# 07_-_QSFP28_2.net
KiCad netlist of a schematic drawn in Altium Designer
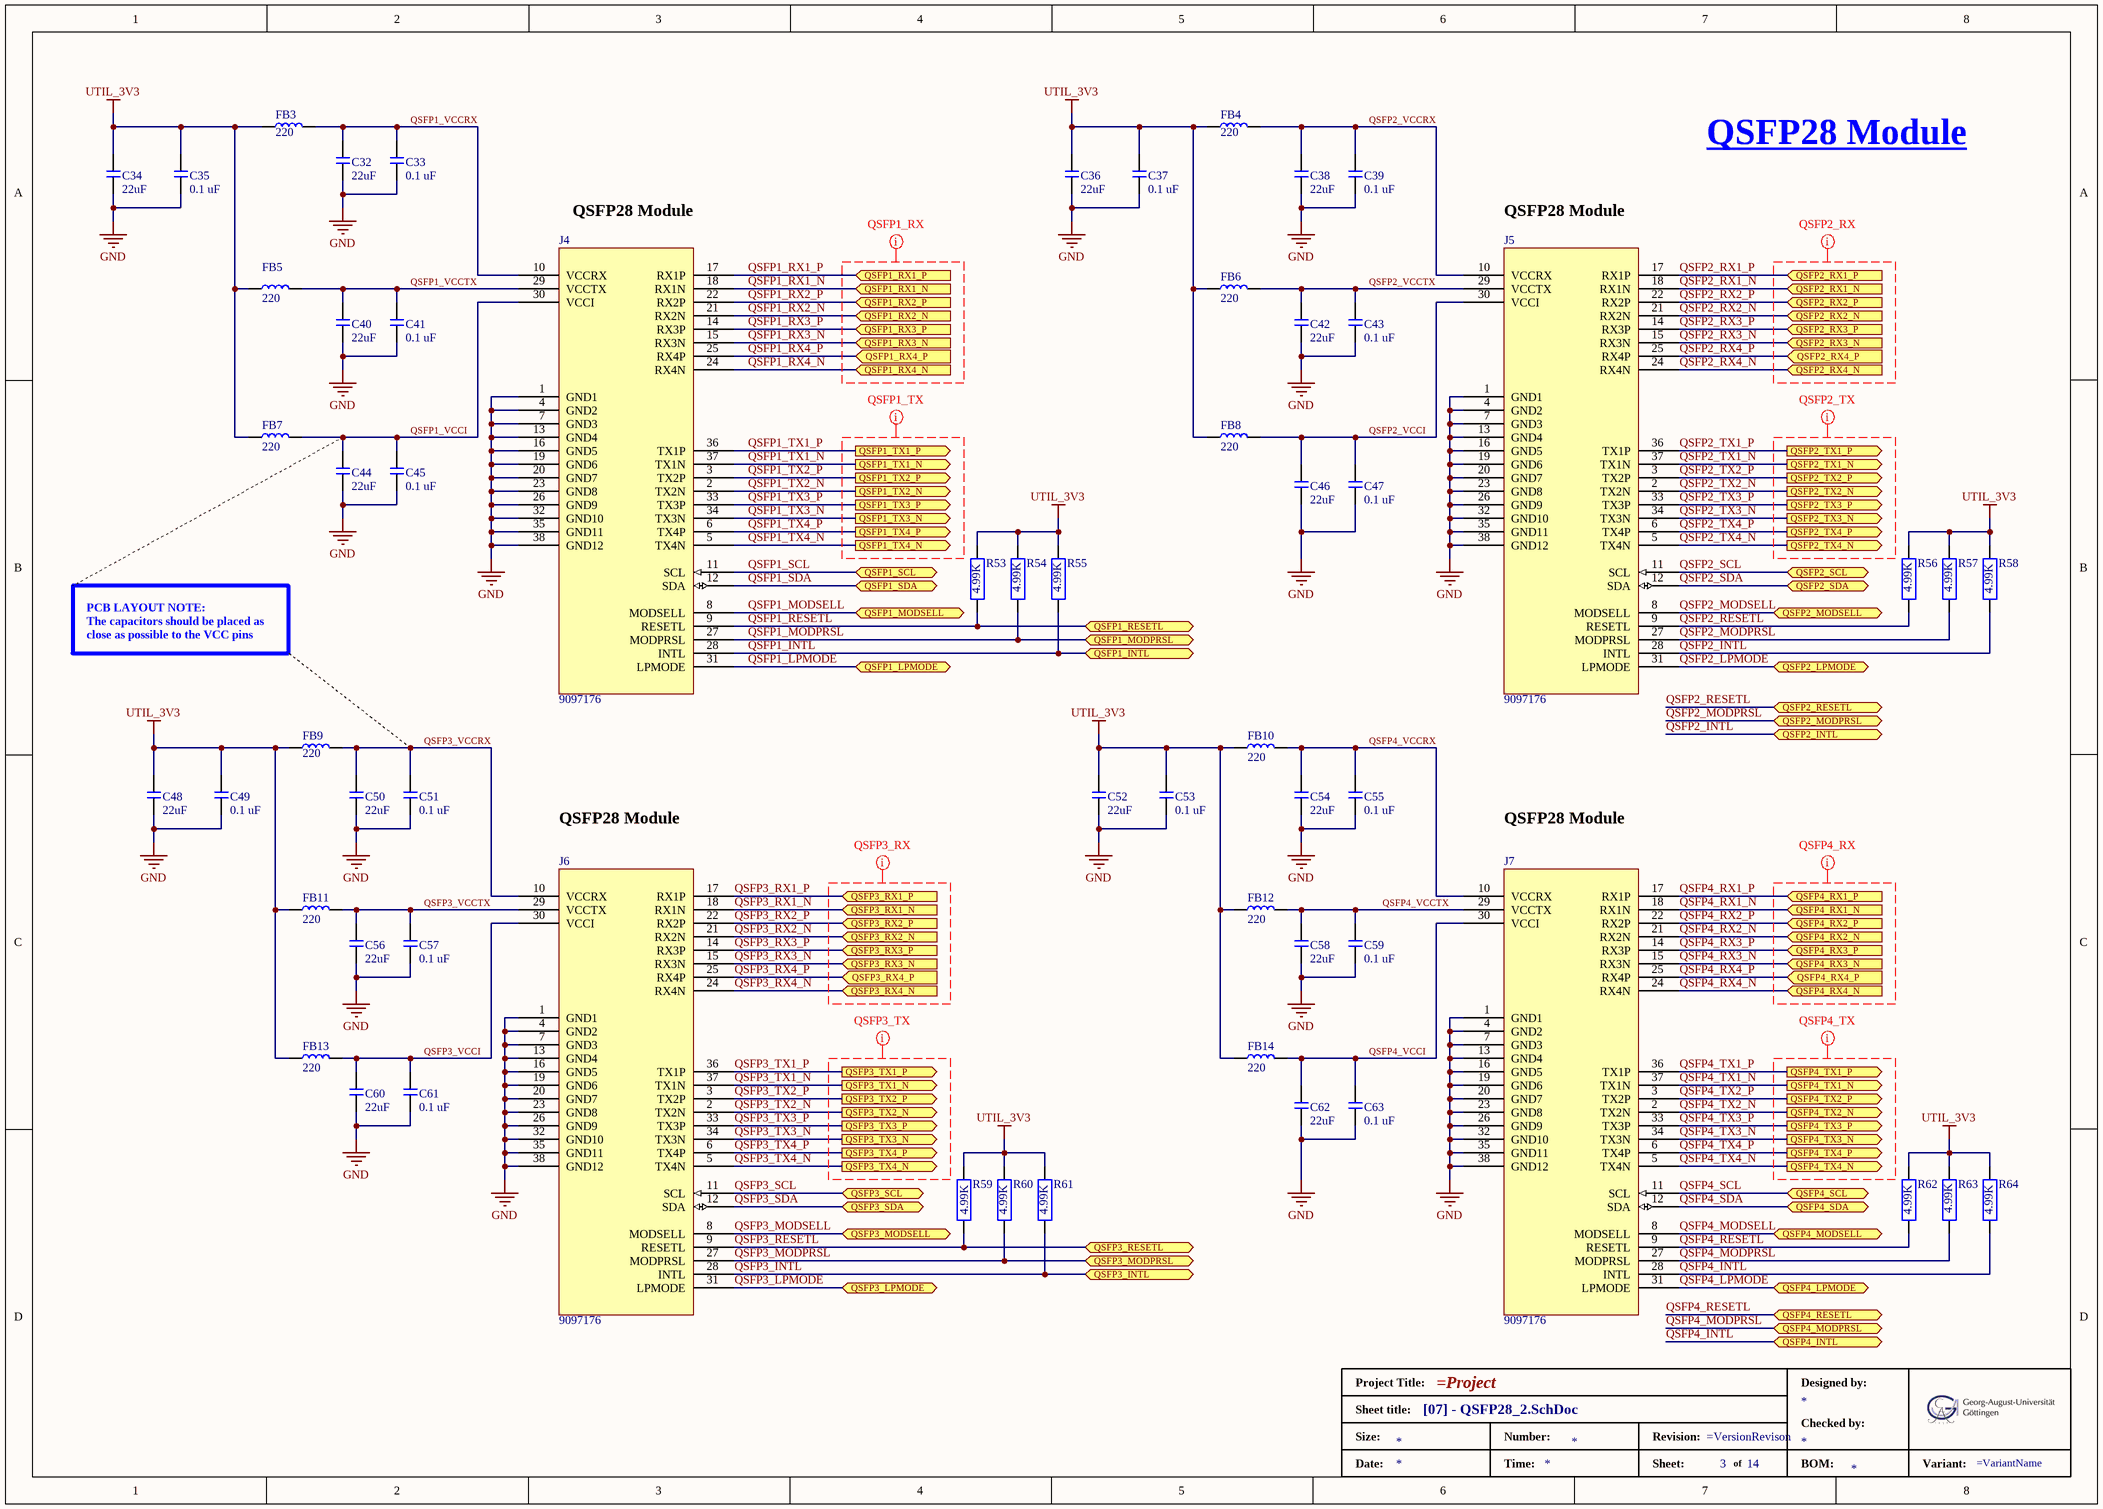
[diagram p0: [07] - QSFP28_2.SchDoc]

(export (version "E")
  (design (tool "Eeschema 10.0.6"))
  (components
    (comp (ref "*")
      (value "Standard Title Block")
      (fields
        (field (name "SIZE") "*")
        (field (name "BOM") "*")
        (field (name "DESIGNEDBY") "*")
        (field (name "DW") "*")
        (field (name "CHECKEDBY") "*")
      )
      (libsource (lib "QSFP28_FMC_lib") (part "Title_Block"))
    )
    (comp (ref "C32")
      (value "22uF")
      (footprint "C2012")
      (description "Cap Series 0805 22 uF 35 V ±20 % Tolerance X5R SMT Multilayer Ceramic Capacitor")
      (fields
        (field (name "MANUFACTURER") "TDK")
        (field (name "MANUFACTURER PART NUMBER") "C2012X5R1V226M125AC")
      )
      (libsource (lib "QSFP28_FMC_lib") (part "C2012X5R1V226M125AC"))
    )
    (comp (ref "C33")
      (value "0.1 uF")
      (footprint "C0402")
      (description "Cap 0402 0.1 uF 50 V ±10 % Tolerance X7R Surface Mount Multilayer Ceramic Capacitor")
      (fields
        (field (name "MANUFACTURER") "Taiyo Yuden")
        (field (name "MANUFACTURER PART NUMBER") "UMK105B7104KV-FR")
      )
      (libsource (lib "QSFP28_FMC_lib") (part "UMK105B7104KV-FR"))
    )
    (comp (ref "C34")
      (value "22uF")
      (footprint "C2012")
      (description "Cap Series 0805 22 uF 35 V ±20 % Tolerance X5R SMT Multilayer Ceramic Capacitor")
      (fields
        (field (name "MANUFACTURER") "TDK")
        (field (name "MANUFACTURER PART NUMBER") "C2012X5R1V226M125AC")
      )
      (libsource (lib "QSFP28_FMC_lib") (part "C2012X5R1V226M125AC"))
    )
    (comp (ref "C35")
      (value "0.1 uF")
      (footprint "C0402")
      (description "Cap 0402 0.1 uF 50 V ±10 % Tolerance X7R Surface Mount Multilayer Ceramic Capacitor")
      (fields
        (field (name "MANUFACTURER") "Taiyo Yuden")
        (field (name "MANUFACTURER PART NUMBER") "UMK105B7104KV-FR")
      )
      (libsource (lib "QSFP28_FMC_lib") (part "UMK105B7104KV-FR"))
    )
    (comp (ref "C36")
      (value "22uF")
      (footprint "C2012")
      (description "Cap Series 0805 22 uF 35 V ±20 % Tolerance X5R SMT Multilayer Ceramic Capacitor")
      (fields
        (field (name "MANUFACTURER") "TDK")
        (field (name "MANUFACTURER PART NUMBER") "C2012X5R1V226M125AC")
      )
      (libsource (lib "QSFP28_FMC_lib") (part "C2012X5R1V226M125AC"))
    )
    (comp (ref "C37")
      (value "0.1 uF")
      (footprint "C0402")
      (description "Cap 0402 0.1 uF 50 V ±10 % Tolerance X7R Surface Mount Multilayer Ceramic Capacitor")
      (fields
        (field (name "MANUFACTURER") "Taiyo Yuden")
        (field (name "MANUFACTURER PART NUMBER") "UMK105B7104KV-FR")
      )
      (libsource (lib "QSFP28_FMC_lib") (part "UMK105B7104KV-FR"))
    )
    (comp (ref "C38")
      (value "22uF")
      (footprint "C2012")
      (description "Cap Series 0805 22 uF 35 V ±20 % Tolerance X5R SMT Multilayer Ceramic Capacitor")
      (fields
        (field (name "MANUFACTURER") "TDK")
        (field (name "MANUFACTURER PART NUMBER") "C2012X5R1V226M125AC")
      )
      (libsource (lib "QSFP28_FMC_lib") (part "C2012X5R1V226M125AC"))
    )
    (comp (ref "C39")
      (value "0.1 uF")
      (footprint "C0402")
      (description "Cap 0402 0.1 uF 50 V ±10 % Tolerance X7R Surface Mount Multilayer Ceramic Capacitor")
      (fields
        (field (name "MANUFACTURER") "Taiyo Yuden")
        (field (name "MANUFACTURER PART NUMBER") "UMK105B7104KV-FR")
      )
      (libsource (lib "QSFP28_FMC_lib") (part "UMK105B7104KV-FR"))
    )
    (comp (ref "C40")
      (value "22uF")
      (footprint "C2012")
      (description "Cap Series 0805 22 uF 35 V ±20 % Tolerance X5R SMT Multilayer Ceramic Capacitor")
      (fields
        (field (name "MANUFACTURER") "TDK")
        (field (name "MANUFACTURER PART NUMBER") "C2012X5R1V226M125AC")
      )
      (libsource (lib "QSFP28_FMC_lib") (part "C2012X5R1V226M125AC"))
    )
    (comp (ref "C41")
      (value "0.1 uF")
      (footprint "C0402")
      (description "Cap 0402 0.1 uF 50 V ±10 % Tolerance X7R Surface Mount Multilayer Ceramic Capacitor")
      (fields
        (field (name "MANUFACTURER") "Taiyo Yuden")
        (field (name "MANUFACTURER PART NUMBER") "UMK105B7104KV-FR")
      )
      (libsource (lib "QSFP28_FMC_lib") (part "UMK105B7104KV-FR"))
    )
    (comp (ref "C42")
      (value "22uF")
      (footprint "C2012")
      (description "Cap Series 0805 22 uF 35 V ±20 % Tolerance X5R SMT Multilayer Ceramic Capacitor")
      (fields
        (field (name "MANUFACTURER") "TDK")
        (field (name "MANUFACTURER PART NUMBER") "C2012X5R1V226M125AC")
      )
      (libsource (lib "QSFP28_FMC_lib") (part "C2012X5R1V226M125AC"))
    )
    (comp (ref "C43")
      (value "0.1 uF")
      (footprint "C0402")
      (description "Cap 0402 0.1 uF 50 V ±10 % Tolerance X7R Surface Mount Multilayer Ceramic Capacitor")
      (fields
        (field (name "MANUFACTURER") "Taiyo Yuden")
        (field (name "MANUFACTURER PART NUMBER") "UMK105B7104KV-FR")
      )
      (libsource (lib "QSFP28_FMC_lib") (part "UMK105B7104KV-FR"))
    )
    (comp (ref "C44")
      (value "22uF")
      (footprint "C2012")
      (description "Cap Series 0805 22 uF 35 V ±20 % Tolerance X5R SMT Multilayer Ceramic Capacitor")
      (fields
        (field (name "MANUFACTURER") "TDK")
        (field (name "MANUFACTURER PART NUMBER") "C2012X5R1V226M125AC")
      )
      (libsource (lib "QSFP28_FMC_lib") (part "C2012X5R1V226M125AC"))
    )
    (comp (ref "C45")
      (value "0.1 uF")
      (footprint "C0402")
      (description "Cap 0402 0.1 uF 50 V ±10 % Tolerance X7R Surface Mount Multilayer Ceramic Capacitor")
      (fields
        (field (name "MANUFACTURER") "Taiyo Yuden")
        (field (name "MANUFACTURER PART NUMBER") "UMK105B7104KV-FR")
      )
      (libsource (lib "QSFP28_FMC_lib") (part "UMK105B7104KV-FR"))
    )
    (comp (ref "C46")
      (value "22uF")
      (footprint "C2012")
      (description "Cap Series 0805 22 uF 35 V ±20 % Tolerance X5R SMT Multilayer Ceramic Capacitor")
      (fields
        (field (name "MANUFACTURER") "TDK")
        (field (name "MANUFACTURER PART NUMBER") "C2012X5R1V226M125AC")
      )
      (libsource (lib "QSFP28_FMC_lib") (part "C2012X5R1V226M125AC"))
    )
    (comp (ref "C47")
      (value "0.1 uF")
      (footprint "C0402")
      (description "Cap 0402 0.1 uF 50 V ±10 % Tolerance X7R Surface Mount Multilayer Ceramic Capacitor")
      (fields
        (field (name "MANUFACTURER") "Taiyo Yuden")
        (field (name "MANUFACTURER PART NUMBER") "UMK105B7104KV-FR")
      )
      (libsource (lib "QSFP28_FMC_lib") (part "UMK105B7104KV-FR"))
    )
    (comp (ref "C48")
      (value "22uF")
      (footprint "C2012")
      (description "Cap Series 0805 22 uF 35 V ±20 % Tolerance X5R SMT Multilayer Ceramic Capacitor")
      (fields
        (field (name "MANUFACTURER") "TDK")
        (field (name "MANUFACTURER PART NUMBER") "C2012X5R1V226M125AC")
      )
      (libsource (lib "QSFP28_FMC_lib") (part "C2012X5R1V226M125AC"))
    )
    (comp (ref "C49")
      (value "0.1 uF")
      (footprint "C0402")
      (description "Cap 0402 0.1 uF 50 V ±10 % Tolerance X7R Surface Mount Multilayer Ceramic Capacitor")
      (fields
        (field (name "MANUFACTURER") "Taiyo Yuden")
        (field (name "MANUFACTURER PART NUMBER") "UMK105B7104KV-FR")
      )
      (libsource (lib "QSFP28_FMC_lib") (part "UMK105B7104KV-FR"))
    )
    (comp (ref "C50")
      (value "22uF")
      (footprint "C2012")
      (description "Cap Series 0805 22 uF 35 V ±20 % Tolerance X5R SMT Multilayer Ceramic Capacitor")
      (fields
        (field (name "MANUFACTURER") "TDK")
        (field (name "MANUFACTURER PART NUMBER") "C2012X5R1V226M125AC")
      )
      (libsource (lib "QSFP28_FMC_lib") (part "C2012X5R1V226M125AC"))
    )
    (comp (ref "C51")
      (value "0.1 uF")
      (footprint "C0402")
      (description "Cap 0402 0.1 uF 50 V ±10 % Tolerance X7R Surface Mount Multilayer Ceramic Capacitor")
      (fields
        (field (name "MANUFACTURER") "Taiyo Yuden")
        (field (name "MANUFACTURER PART NUMBER") "UMK105B7104KV-FR")
      )
      (libsource (lib "QSFP28_FMC_lib") (part "UMK105B7104KV-FR"))
    )
    (comp (ref "C52")
      (value "22uF")
      (footprint "C2012")
      (description "Cap Series 0805 22 uF 35 V ±20 % Tolerance X5R SMT Multilayer Ceramic Capacitor")
      (fields
        (field (name "MANUFACTURER") "TDK")
        (field (name "MANUFACTURER PART NUMBER") "C2012X5R1V226M125AC")
      )
      (libsource (lib "QSFP28_FMC_lib") (part "C2012X5R1V226M125AC"))
    )
    (comp (ref "C53")
      (value "0.1 uF")
      (footprint "C0402")
      (description "Cap 0402 0.1 uF 50 V ±10 % Tolerance X7R Surface Mount Multilayer Ceramic Capacitor")
      (fields
        (field (name "MANUFACTURER") "Taiyo Yuden")
        (field (name "MANUFACTURER PART NUMBER") "UMK105B7104KV-FR")
      )
      (libsource (lib "QSFP28_FMC_lib") (part "UMK105B7104KV-FR"))
    )
    (comp (ref "C54")
      (value "22uF")
      (footprint "C2012")
      (description "Cap Series 0805 22 uF 35 V ±20 % Tolerance X5R SMT Multilayer Ceramic Capacitor")
      (fields
        (field (name "MANUFACTURER") "TDK")
        (field (name "MANUFACTURER PART NUMBER") "C2012X5R1V226M125AC")
      )
      (libsource (lib "QSFP28_FMC_lib") (part "C2012X5R1V226M125AC"))
    )
    (comp (ref "C55")
      (value "0.1 uF")
      (footprint "C0402")
      (description "Cap 0402 0.1 uF 50 V ±10 % Tolerance X7R Surface Mount Multilayer Ceramic Capacitor")
      (fields
        (field (name "MANUFACTURER") "Taiyo Yuden")
        (field (name "MANUFACTURER PART NUMBER") "UMK105B7104KV-FR")
      )
      (libsource (lib "QSFP28_FMC_lib") (part "UMK105B7104KV-FR"))
    )
    (comp (ref "C56")
      (value "22uF")
      (footprint "C2012")
      (description "Cap Series 0805 22 uF 35 V ±20 % Tolerance X5R SMT Multilayer Ceramic Capacitor")
      (fields
        (field (name "MANUFACTURER") "TDK")
        (field (name "MANUFACTURER PART NUMBER") "C2012X5R1V226M125AC")
      )
      (libsource (lib "QSFP28_FMC_lib") (part "C2012X5R1V226M125AC"))
    )
    (comp (ref "C57")
      (value "0.1 uF")
      (footprint "C0402")
      (description "Cap 0402 0.1 uF 50 V ±10 % Tolerance X7R Surface Mount Multilayer Ceramic Capacitor")
      (fields
        (field (name "MANUFACTURER") "Taiyo Yuden")
        (field (name "MANUFACTURER PART NUMBER") "UMK105B7104KV-FR")
      )
      (libsource (lib "QSFP28_FMC_lib") (part "UMK105B7104KV-FR"))
    )
    (comp (ref "C58")
      (value "22uF")
      (footprint "C2012")
      (description "Cap Series 0805 22 uF 35 V ±20 % Tolerance X5R SMT Multilayer Ceramic Capacitor")
      (fields
        (field (name "MANUFACTURER") "TDK")
        (field (name "MANUFACTURER PART NUMBER") "C2012X5R1V226M125AC")
      )
      (libsource (lib "QSFP28_FMC_lib") (part "C2012X5R1V226M125AC"))
    )
    (comp (ref "C59")
      (value "0.1 uF")
      (footprint "C0402")
      (description "Cap 0402 0.1 uF 50 V ±10 % Tolerance X7R Surface Mount Multilayer Ceramic Capacitor")
      (fields
        (field (name "MANUFACTURER") "Taiyo Yuden")
        (field (name "MANUFACTURER PART NUMBER") "UMK105B7104KV-FR")
      )
      (libsource (lib "QSFP28_FMC_lib") (part "UMK105B7104KV-FR"))
    )
    (comp (ref "C60")
      (value "22uF")
      (footprint "C2012")
      (description "Cap Series 0805 22 uF 35 V ±20 % Tolerance X5R SMT Multilayer Ceramic Capacitor")
      (fields
        (field (name "MANUFACTURER") "TDK")
        (field (name "MANUFACTURER PART NUMBER") "C2012X5R1V226M125AC")
      )
      (libsource (lib "QSFP28_FMC_lib") (part "C2012X5R1V226M125AC"))
    )
    (comp (ref "C61")
      (value "0.1 uF")
      (footprint "C0402")
      (description "Cap 0402 0.1 uF 50 V ±10 % Tolerance X7R Surface Mount Multilayer Ceramic Capacitor")
      (fields
        (field (name "MANUFACTURER") "Taiyo Yuden")
        (field (name "MANUFACTURER PART NUMBER") "UMK105B7104KV-FR")
      )
      (libsource (lib "QSFP28_FMC_lib") (part "UMK105B7104KV-FR"))
    )
    (comp (ref "C62")
      (value "22uF")
      (footprint "C2012")
      (description "Cap Series 0805 22 uF 35 V ±20 % Tolerance X5R SMT Multilayer Ceramic Capacitor")
      (fields
        (field (name "MANUFACTURER") "TDK")
        (field (name "MANUFACTURER PART NUMBER") "C2012X5R1V226M125AC")
      )
      (libsource (lib "QSFP28_FMC_lib") (part "C2012X5R1V226M125AC"))
    )
    (comp (ref "C63")
      (value "0.1 uF")
      (footprint "C0402")
      (description "Cap 0402 0.1 uF 50 V ±10 % Tolerance X7R Surface Mount Multilayer Ceramic Capacitor")
      (fields
        (field (name "MANUFACTURER") "Taiyo Yuden")
        (field (name "MANUFACTURER PART NUMBER") "UMK105B7104KV-FR")
      )
      (libsource (lib "QSFP28_FMC_lib") (part "UMK105B7104KV-FR"))
    )
    (comp (ref "FB3")
      (value "220")
      (footprint "BEADC1608X75N")
      (description "0603 220Ω ±25% DCR=0.050Ω 2.2A")
      (fields
        (field (name "MANUFACTURER") "TDK")
        (field (name "MANUFACTURER PART NUMBER") "MPZ1608S221ATA00")
      )
      (libsource (lib "QSFP28_FMC_lib") (part "MPZ1608S221ATA00"))
    )
    (comp (ref "FB4")
      (value "220")
      (footprint "BEADC1608X75N")
      (description "0603 220Ω ±25% DCR=0.050Ω 2.2A")
      (fields
        (field (name "MANUFACTURER") "TDK")
        (field (name "MANUFACTURER PART NUMBER") "MPZ1608S221ATA00")
      )
      (libsource (lib "QSFP28_FMC_lib") (part "MPZ1608S221ATA00"))
    )
    (comp (ref "FB5")
      (value "220")
      (footprint "BEADC1608X75N")
      (description "0603 220Ω ±25% DCR=0.050Ω 2.2A")
      (fields
        (field (name "MANUFACTURER") "TDK")
        (field (name "MANUFACTURER PART NUMBER") "MPZ1608S221ATA00")
      )
      (libsource (lib "QSFP28_FMC_lib") (part "MPZ1608S221ATA00"))
    )
    (comp (ref "FB6")
      (value "220")
      (footprint "BEADC1608X75N")
      (description "0603 220Ω ±25% DCR=0.050Ω 2.2A")
      (fields
        (field (name "MANUFACTURER") "TDK")
        (field (name "MANUFACTURER PART NUMBER") "MPZ1608S221ATA00")
      )
      (libsource (lib "QSFP28_FMC_lib") (part "MPZ1608S221ATA00"))
    )
    (comp (ref "FB7")
      (value "220")
      (footprint "BEADC1608X75N")
      (description "0603 220Ω ±25% DCR=0.050Ω 2.2A")
      (fields
        (field (name "MANUFACTURER") "TDK")
        (field (name "MANUFACTURER PART NUMBER") "MPZ1608S221ATA00")
      )
      (libsource (lib "QSFP28_FMC_lib") (part "MPZ1608S221ATA00"))
    )
    (comp (ref "FB8")
      (value "220")
      (footprint "BEADC1608X75N")
      (description "0603 220Ω ±25% DCR=0.050Ω 2.2A")
      (fields
        (field (name "MANUFACTURER") "TDK")
        (field (name "MANUFACTURER PART NUMBER") "MPZ1608S221ATA00")
      )
      (libsource (lib "QSFP28_FMC_lib") (part "MPZ1608S221ATA00"))
    )
    (comp (ref "FB9")
      (value "220")
      (footprint "BEADC1608X75N")
      (description "0603 220Ω ±25% DCR=0.050Ω 2.2A")
      (fields
        (field (name "MANUFACTURER") "TDK")
        (field (name "MANUFACTURER PART NUMBER") "MPZ1608S221ATA00")
      )
      (libsource (lib "QSFP28_FMC_lib") (part "MPZ1608S221ATA00"))
    )
    (comp (ref "FB10")
      (value "220")
      (footprint "BEADC1608X75N")
      (description "0603 220Ω ±25% DCR=0.050Ω 2.2A")
      (fields
        (field (name "MANUFACTURER") "TDK")
        (field (name "MANUFACTURER PART NUMBER") "MPZ1608S221ATA00")
      )
      (libsource (lib "QSFP28_FMC_lib") (part "MPZ1608S221ATA00"))
    )
    (comp (ref "FB11")
      (value "220")
      (footprint "BEADC1608X75N")
      (description "0603 220Ω ±25% DCR=0.050Ω 2.2A")
      (fields
        (field (name "MANUFACTURER") "TDK")
        (field (name "MANUFACTURER PART NUMBER") "MPZ1608S221ATA00")
      )
      (libsource (lib "QSFP28_FMC_lib") (part "MPZ1608S221ATA00"))
    )
    (comp (ref "FB12")
      (value "220")
      (footprint "BEADC1608X75N")
      (description "0603 220Ω ±25% DCR=0.050Ω 2.2A")
      (fields
        (field (name "MANUFACTURER") "TDK")
        (field (name "MANUFACTURER PART NUMBER") "MPZ1608S221ATA00")
      )
      (libsource (lib "QSFP28_FMC_lib") (part "MPZ1608S221ATA00"))
    )
    (comp (ref "FB13")
      (value "220")
      (footprint "BEADC1608X75N")
      (description "0603 220Ω ±25% DCR=0.050Ω 2.2A")
      (fields
        (field (name "MANUFACTURER") "TDK")
        (field (name "MANUFACTURER PART NUMBER") "MPZ1608S221ATA00")
      )
      (libsource (lib "QSFP28_FMC_lib") (part "MPZ1608S221ATA00"))
    )
    (comp (ref "FB14")
      (value "220")
      (footprint "BEADC1608X75N")
      (description "0603 220Ω ±25% DCR=0.050Ω 2.2A")
      (fields
        (field (name "MANUFACTURER") "TDK")
        (field (name "MANUFACTURER PART NUMBER") "MPZ1608S221ATA00")
      )
      (libsource (lib "QSFP28_FMC_lib") (part "MPZ1608S221ATA00"))
    )
    (comp (ref "J4")
      (value "ZQSFP+")
      (footprint "TE_1551920-2")
      (description "38 Position Receptacle Surface Mount Right Angle ZQSFP+ Connector")
      (fields
        (field (name "MANUFACTURER") "TE Connectivity AMP")
        (field (name "MANUFACTURER PART NUMBER") "1551920-2")
        (field (name "SUPPLIER PART NUMBER 1") "9097176")
      )
      (libsource (lib "QSFP28_FMC_lib") (part "1551920-2"))
    )
    (comp (ref "J5")
      (value "ZQSFP+")
      (footprint "TE_1551920-2")
      (description "38 Position Receptacle Surface Mount Right Angle ZQSFP+ Connector")
      (fields
        (field (name "MANUFACTURER") "TE Connectivity AMP")
        (field (name "MANUFACTURER PART NUMBER") "1551920-2")
        (field (name "SUPPLIER PART NUMBER 1") "9097176")
      )
      (libsource (lib "QSFP28_FMC_lib") (part "1551920-2"))
    )
    (comp (ref "J6")
      (value "ZQSFP+")
      (footprint "TE_1551920-2")
      (description "38 Position Receptacle Surface Mount Right Angle ZQSFP+ Connector")
      (fields
        (field (name "MANUFACTURER") "TE Connectivity AMP")
        (field (name "MANUFACTURER PART NUMBER") "1551920-2")
        (field (name "SUPPLIER PART NUMBER 1") "9097176")
      )
      (libsource (lib "QSFP28_FMC_lib") (part "1551920-2"))
    )
    (comp (ref "J7")
      (value "ZQSFP+")
      (footprint "TE_1551920-2")
      (description "38 Position Receptacle Surface Mount Right Angle ZQSFP+ Connector")
      (fields
        (field (name "MANUFACTURER") "TE Connectivity AMP")
        (field (name "MANUFACTURER PART NUMBER") "1551920-2")
        (field (name "SUPPLIER PART NUMBER 1") "9097176")
      )
      (libsource (lib "QSFP28_FMC_lib") (part "1551920-2"))
    )
    (comp (ref "R53")
      (value "4.99K")
      (footprint "R0402")
      (description "RES SMD 4.99K OHM 1% 1/10W 0402")
      (fields
        (field (name "MANUFACTURER") "Panasonic")
        (field (name "MANUFACTURER PART NUMBER") "ERJ-2RKF4991X")
      )
      (libsource (lib "QSFP28_FMC_lib") (part "ERJ-2RKF4991X"))
    )
    (comp (ref "R54")
      (value "4.99K")
      (footprint "R0402")
      (description "RES SMD 4.99K OHM 1% 1/10W 0402")
      (fields
        (field (name "MANUFACTURER") "Panasonic")
        (field (name "MANUFACTURER PART NUMBER") "ERJ-2RKF4991X")
      )
      (libsource (lib "QSFP28_FMC_lib") (part "ERJ-2RKF4991X"))
    )
    (comp (ref "R55")
      (value "4.99K")
      (footprint "R0402")
      (description "RES SMD 4.99K OHM 1% 1/10W 0402")
      (fields
        (field (name "MANUFACTURER") "Panasonic")
        (field (name "MANUFACTURER PART NUMBER") "ERJ-2RKF4991X")
      )
      (libsource (lib "QSFP28_FMC_lib") (part "ERJ-2RKF4991X"))
    )
    (comp (ref "R56")
      (value "4.99K")
      (footprint "R0402")
      (description "RES SMD 4.99K OHM 1% 1/10W 0402")
      (fields
        (field (name "MANUFACTURER") "Panasonic")
        (field (name "MANUFACTURER PART NUMBER") "ERJ-2RKF4991X")
      )
      (libsource (lib "QSFP28_FMC_lib") (part "ERJ-2RKF4991X"))
    )
    (comp (ref "R57")
      (value "4.99K")
      (footprint "R0402")
      (description "RES SMD 4.99K OHM 1% 1/10W 0402")
      (fields
        (field (name "MANUFACTURER") "Panasonic")
        (field (name "MANUFACTURER PART NUMBER") "ERJ-2RKF4991X")
      )
      (libsource (lib "QSFP28_FMC_lib") (part "ERJ-2RKF4991X"))
    )
    (comp (ref "R58")
      (value "4.99K")
      (footprint "R0402")
      (description "RES SMD 4.99K OHM 1% 1/10W 0402")
      (fields
        (field (name "MANUFACTURER") "Panasonic")
        (field (name "MANUFACTURER PART NUMBER") "ERJ-2RKF4991X")
      )
      (libsource (lib "QSFP28_FMC_lib") (part "ERJ-2RKF4991X"))
    )
    (comp (ref "R59")
      (value "4.99K")
      (footprint "R0402")
      (description "RES SMD 4.99K OHM 1% 1/10W 0402")
      (fields
        (field (name "MANUFACTURER") "Panasonic")
        (field (name "MANUFACTURER PART NUMBER") "ERJ-2RKF4991X")
      )
      (libsource (lib "QSFP28_FMC_lib") (part "ERJ-2RKF4991X"))
    )
    (comp (ref "R60")
      (value "4.99K")
      (footprint "R0402")
      (description "RES SMD 4.99K OHM 1% 1/10W 0402")
      (fields
        (field (name "MANUFACTURER") "Panasonic")
        (field (name "MANUFACTURER PART NUMBER") "ERJ-2RKF4991X")
      )
      (libsource (lib "QSFP28_FMC_lib") (part "ERJ-2RKF4991X"))
    )
    (comp (ref "R61")
      (value "4.99K")
      (footprint "R0402")
      (description "RES SMD 4.99K OHM 1% 1/10W 0402")
      (fields
        (field (name "MANUFACTURER") "Panasonic")
        (field (name "MANUFACTURER PART NUMBER") "ERJ-2RKF4991X")
      )
      (libsource (lib "QSFP28_FMC_lib") (part "ERJ-2RKF4991X"))
    )
    (comp (ref "R62")
      (value "4.99K")
      (footprint "R0402")
      (description "RES SMD 4.99K OHM 1% 1/10W 0402")
      (fields
        (field (name "MANUFACTURER") "Panasonic")
        (field (name "MANUFACTURER PART NUMBER") "ERJ-2RKF4991X")
      )
      (libsource (lib "QSFP28_FMC_lib") (part "ERJ-2RKF4991X"))
    )
    (comp (ref "R63")
      (value "4.99K")
      (footprint "R0402")
      (description "RES SMD 4.99K OHM 1% 1/10W 0402")
      (fields
        (field (name "MANUFACTURER") "Panasonic")
        (field (name "MANUFACTURER PART NUMBER") "ERJ-2RKF4991X")
      )
      (libsource (lib "QSFP28_FMC_lib") (part "ERJ-2RKF4991X"))
    )
    (comp (ref "R64")
      (value "4.99K")
      (footprint "R0402")
      (description "RES SMD 4.99K OHM 1% 1/10W 0402")
      (fields
        (field (name "MANUFACTURER") "Panasonic")
        (field (name "MANUFACTURER PART NUMBER") "ERJ-2RKF4991X")
      )
      (libsource (lib "QSFP28_FMC_lib") (part "ERJ-2RKF4991X"))
    )
  )
  (nets
    (net (code "1") (name "/QSFP1_INTL") (class "Default")
      (node (ref "J4") (pin "28") (pinfunction "INTL_28") (pintype "passive"))
      (node (ref "R55") (pin "1") (pintype "passive"))
    )
    (net (code "2") (name "/QSFP1_LPMODE") (class "Default")
      (node (ref "J4") (pin "31") (pinfunction "LPMODE_31") (pintype "passive"))
    )
    (net (code "3") (name "/QSFP1_MODPRSL") (class "Default")
      (node (ref "J4") (pin "27") (pinfunction "MODPRSL_27") (pintype "passive"))
      (node (ref "R54") (pin "1") (pintype "passive"))
    )
    (net (code "4") (name "/QSFP1_MODSELL") (class "Default")
      (node (ref "J4") (pin "8") (pinfunction "MODSELL_8") (pintype "passive"))
    )
    (net (code "5") (name "/QSFP1_RESETL") (class "Default")
      (node (ref "J4") (pin "9") (pinfunction "RESETL_9") (pintype "passive"))
      (node (ref "R53") (pin "1") (pintype "passive"))
    )
    (net (code "6") (name "/QSFP1_RX1_N") (class "Default")
      (node (ref "J4") (pin "18") (pinfunction "RX1N_18") (pintype "passive"))
    )
    (net (code "7") (name "/QSFP1_RX1_P") (class "Default")
      (node (ref "J4") (pin "17") (pinfunction "RX1P_17") (pintype "passive"))
    )
    (net (code "8") (name "/QSFP1_RX2_N") (class "Default")
      (node (ref "J4") (pin "21") (pinfunction "RX2N_21") (pintype "passive"))
    )
    (net (code "9") (name "/QSFP1_RX2_P") (class "Default")
      (node (ref "J4") (pin "22") (pinfunction "RX2P_22") (pintype "passive"))
    )
    (net (code "10") (name "/QSFP1_RX3_N") (class "Default")
      (node (ref "J4") (pin "15") (pinfunction "RX3N_15") (pintype "passive"))
    )
    (net (code "11") (name "/QSFP1_RX3_P") (class "Default")
      (node (ref "J4") (pin "14") (pinfunction "RX3P_14") (pintype "passive"))
    )
    (net (code "12") (name "/QSFP1_RX4_N") (class "Default")
      (node (ref "J4") (pin "24") (pinfunction "RX4N_24") (pintype "passive"))
    )
    (net (code "13") (name "/QSFP1_RX4_P") (class "Default")
      (node (ref "J4") (pin "25") (pinfunction "RX4P_25") (pintype "passive"))
    )
    (net (code "14") (name "/QSFP1_SCL") (class "Default")
      (node (ref "J4") (pin "11") (pinfunction "SCL_11") (pintype "input"))
    )
    (net (code "15") (name "/QSFP1_SDA") (class "Default")
      (node (ref "J4") (pin "12") (pinfunction "SDA_12") (pintype "bidirectional"))
    )
    (net (code "16") (name "/QSFP1_TX1_N") (class "Default")
      (node (ref "J4") (pin "37") (pinfunction "TX1N_37") (pintype "passive"))
    )
    (net (code "17") (name "/QSFP1_TX1_P") (class "Default")
      (node (ref "J4") (pin "36") (pinfunction "TX1P_36") (pintype "passive"))
    )
    (net (code "18") (name "/QSFP1_TX2_N") (class "Default")
      (node (ref "J4") (pin "2") (pinfunction "TX2N_2") (pintype "passive"))
    )
    (net (code "19") (name "/QSFP1_TX2_P") (class "Default")
      (node (ref "J4") (pin "3") (pinfunction "TX2P_3") (pintype "passive"))
    )
    (net (code "20") (name "/QSFP1_TX3_N") (class "Default")
      (node (ref "J4") (pin "34") (pinfunction "TX3N_34") (pintype "passive"))
    )
    (net (code "21") (name "/QSFP1_TX3_P") (class "Default")
      (node (ref "J4") (pin "33") (pinfunction "TX3P_33") (pintype "passive"))
    )
    (net (code "22") (name "/QSFP1_TX4_N") (class "Default")
      (node (ref "J4") (pin "5") (pinfunction "TX4N_5") (pintype "passive"))
    )
    (net (code "23") (name "/QSFP1_TX4_P") (class "Default")
      (node (ref "J4") (pin "6") (pinfunction "TX4P_6") (pintype "passive"))
    )
    (net (code "24") (name "/QSFP1_VCCI") (class "Default")
      (node (ref "C44") (pin "2") (pinfunction "2_2") (pintype "passive"))
      (node (ref "C45") (pin "2") (pinfunction "2_2") (pintype "passive"))
      (node (ref "FB7") (pin "2") (pintype "passive"))
      (node (ref "J4") (pin "30") (pinfunction "VCCI_30") (pintype "power_in"))
    )
    (net (code "25") (name "/QSFP1_VCCRX") (class "Default")
      (node (ref "C32") (pin "2") (pinfunction "2_2") (pintype "passive"))
      (node (ref "C33") (pin "2") (pinfunction "2_2") (pintype "passive"))
      (node (ref "FB3") (pin "2") (pintype "passive"))
      (node (ref "J4") (pin "10") (pinfunction "VCCRX_10") (pintype "power_in"))
    )
    (net (code "26") (name "/QSFP1_VCCTX") (class "Default")
      (node (ref "C40") (pin "2") (pinfunction "2_2") (pintype "passive"))
      (node (ref "C41") (pin "2") (pinfunction "2_2") (pintype "passive"))
      (node (ref "FB5") (pin "2") (pintype "passive"))
      (node (ref "J4") (pin "29") (pinfunction "VCCTX_29") (pintype "power_in"))
    )
    (net (code "27") (name "/QSFP2_INTL") (class "Default")
      (node (ref "J5") (pin "28") (pinfunction "INTL_28") (pintype "passive"))
      (node (ref "R58") (pin "1") (pintype "passive"))
    )
    (net (code "28") (name "/QSFP2_LPMODE") (class "Default")
      (node (ref "J5") (pin "31") (pinfunction "LPMODE_31") (pintype "passive"))
    )
    (net (code "29") (name "/QSFP2_MODPRSL") (class "Default")
      (node (ref "J5") (pin "27") (pinfunction "MODPRSL_27") (pintype "passive"))
      (node (ref "R57") (pin "1") (pintype "passive"))
    )
    (net (code "30") (name "/QSFP2_MODSELL") (class "Default")
      (node (ref "J5") (pin "8") (pinfunction "MODSELL_8") (pintype "passive"))
    )
    (net (code "31") (name "/QSFP2_RESETL") (class "Default")
      (node (ref "J5") (pin "9") (pinfunction "RESETL_9") (pintype "passive"))
      (node (ref "R56") (pin "1") (pintype "passive"))
    )
    (net (code "32") (name "/QSFP2_RX1_N") (class "Default")
      (node (ref "J5") (pin "18") (pinfunction "RX1N_18") (pintype "passive"))
    )
    (net (code "33") (name "/QSFP2_RX1_P") (class "Default")
      (node (ref "J5") (pin "17") (pinfunction "RX1P_17") (pintype "passive"))
    )
    (net (code "34") (name "/QSFP2_RX2_N") (class "Default")
      (node (ref "J5") (pin "21") (pinfunction "RX2N_21") (pintype "passive"))
    )
    (net (code "35") (name "/QSFP2_RX2_P") (class "Default")
      (node (ref "J5") (pin "22") (pinfunction "RX2P_22") (pintype "passive"))
    )
    (net (code "36") (name "/QSFP2_RX3_N") (class "Default")
      (node (ref "J5") (pin "15") (pinfunction "RX3N_15") (pintype "passive"))
    )
    (net (code "37") (name "/QSFP2_RX3_P") (class "Default")
      (node (ref "J5") (pin "14") (pinfunction "RX3P_14") (pintype "passive"))
    )
    (net (code "38") (name "/QSFP2_RX4_N") (class "Default")
      (node (ref "J5") (pin "24") (pinfunction "RX4N_24") (pintype "passive"))
    )
    (net (code "39") (name "/QSFP2_RX4_P") (class "Default")
      (node (ref "J5") (pin "25") (pinfunction "RX4P_25") (pintype "passive"))
    )
    (net (code "40") (name "/QSFP2_SCL") (class "Default")
      (node (ref "J5") (pin "11") (pinfunction "SCL_11") (pintype "input"))
    )
    (net (code "41") (name "/QSFP2_SDA") (class "Default")
      (node (ref "J5") (pin "12") (pinfunction "SDA_12") (pintype "bidirectional"))
    )
    (net (code "42") (name "/QSFP2_TX1_N") (class "Default")
      (node (ref "J5") (pin "37") (pinfunction "TX1N_37") (pintype "passive"))
    )
    (net (code "43") (name "/QSFP2_TX1_P") (class "Default")
      (node (ref "J5") (pin "36") (pinfunction "TX1P_36") (pintype "passive"))
    )
    (net (code "44") (name "/QSFP2_TX2_N") (class "Default")
      (node (ref "J5") (pin "2") (pinfunction "TX2N_2") (pintype "passive"))
    )
    (net (code "45") (name "/QSFP2_TX2_P") (class "Default")
      (node (ref "J5") (pin "3") (pinfunction "TX2P_3") (pintype "passive"))
    )
    (net (code "46") (name "/QSFP2_TX3_N") (class "Default")
      (node (ref "J5") (pin "34") (pinfunction "TX3N_34") (pintype "passive"))
    )
    (net (code "47") (name "/QSFP2_TX3_P") (class "Default")
      (node (ref "J5") (pin "33") (pinfunction "TX3P_33") (pintype "passive"))
    )
    (net (code "48") (name "/QSFP2_TX4_N") (class "Default")
      (node (ref "J5") (pin "5") (pinfunction "TX4N_5") (pintype "passive"))
    )
    (net (code "49") (name "/QSFP2_TX4_P") (class "Default")
      (node (ref "J5") (pin "6") (pinfunction "TX4P_6") (pintype "passive"))
    )
    (net (code "50") (name "/QSFP2_VCCI") (class "Default")
      (node (ref "C46") (pin "2") (pinfunction "2_2") (pintype "passive"))
      (node (ref "C47") (pin "2") (pinfunction "2_2") (pintype "passive"))
      (node (ref "FB8") (pin "2") (pintype "passive"))
      (node (ref "J5") (pin "30") (pinfunction "VCCI_30") (pintype "power_in"))
    )
    (net (code "51") (name "/QSFP2_VCCRX") (class "Default")
      (node (ref "C38") (pin "2") (pinfunction "2_2") (pintype "passive"))
      (node (ref "C39") (pin "2") (pinfunction "2_2") (pintype "passive"))
      (node (ref "FB4") (pin "2") (pintype "passive"))
      (node (ref "J5") (pin "10") (pinfunction "VCCRX_10") (pintype "power_in"))
    )
    (net (code "52") (name "/QSFP2_VCCTX") (class "Default")
      (node (ref "C42") (pin "2") (pinfunction "2_2") (pintype "passive"))
      (node (ref "C43") (pin "2") (pinfunction "2_2") (pintype "passive"))
      (node (ref "FB6") (pin "2") (pintype "passive"))
      (node (ref "J5") (pin "29") (pinfunction "VCCTX_29") (pintype "power_in"))
    )
    (net (code "53") (name "/QSFP3_INTL") (class "Default")
      (node (ref "J6") (pin "28") (pinfunction "INTL_28") (pintype "passive"))
      (node (ref "R61") (pin "1") (pintype "passive"))
    )
    (net (code "54") (name "/QSFP3_LPMODE") (class "Default")
      (node (ref "J6") (pin "31") (pinfunction "LPMODE_31") (pintype "passive"))
    )
    (net (code "55") (name "/QSFP3_MODPRSL") (class "Default")
      (node (ref "J6") (pin "27") (pinfunction "MODPRSL_27") (pintype "passive"))
      (node (ref "R60") (pin "1") (pintype "passive"))
    )
    (net (code "56") (name "/QSFP3_MODSELL") (class "Default")
      (node (ref "J6") (pin "8") (pinfunction "MODSELL_8") (pintype "passive"))
    )
    (net (code "57") (name "/QSFP3_RESETL") (class "Default")
      (node (ref "J6") (pin "9") (pinfunction "RESETL_9") (pintype "passive"))
      (node (ref "R59") (pin "1") (pintype "passive"))
    )
    (net (code "58") (name "/QSFP3_RX1_N") (class "Default")
      (node (ref "J6") (pin "18") (pinfunction "RX1N_18") (pintype "passive"))
    )
    (net (code "59") (name "/QSFP3_RX1_P") (class "Default")
      (node (ref "J6") (pin "17") (pinfunction "RX1P_17") (pintype "passive"))
    )
    (net (code "60") (name "/QSFP3_RX2_N") (class "Default")
      (node (ref "J6") (pin "21") (pinfunction "RX2N_21") (pintype "passive"))
    )
    (net (code "61") (name "/QSFP3_RX2_P") (class "Default")
      (node (ref "J6") (pin "22") (pinfunction "RX2P_22") (pintype "passive"))
    )
    (net (code "62") (name "/QSFP3_RX3_N") (class "Default")
      (node (ref "J6") (pin "15") (pinfunction "RX3N_15") (pintype "passive"))
    )
    (net (code "63") (name "/QSFP3_RX3_P") (class "Default")
      (node (ref "J6") (pin "14") (pinfunction "RX3P_14") (pintype "passive"))
    )
    (net (code "64") (name "/QSFP3_RX4_N") (class "Default")
      (node (ref "J6") (pin "24") (pinfunction "RX4N_24") (pintype "passive"))
    )
    (net (code "65") (name "/QSFP3_RX4_P") (class "Default")
      (node (ref "J6") (pin "25") (pinfunction "RX4P_25") (pintype "passive"))
    )
    (net (code "66") (name "/QSFP3_SCL") (class "Default")
      (node (ref "J6") (pin "11") (pinfunction "SCL_11") (pintype "input"))
    )
    (net (code "67") (name "/QSFP3_SDA") (class "Default")
      (node (ref "J6") (pin "12") (pinfunction "SDA_12") (pintype "bidirectional"))
    )
    (net (code "68") (name "/QSFP3_TX1_N") (class "Default")
      (node (ref "J6") (pin "37") (pinfunction "TX1N_37") (pintype "passive"))
    )
    (net (code "69") (name "/QSFP3_TX1_P") (class "Default")
      (node (ref "J6") (pin "36") (pinfunction "TX1P_36") (pintype "passive"))
    )
    (net (code "70") (name "/QSFP3_TX2_N") (class "Default")
      (node (ref "J6") (pin "2") (pinfunction "TX2N_2") (pintype "passive"))
    )
    (net (code "71") (name "/QSFP3_TX2_P") (class "Default")
      (node (ref "J6") (pin "3") (pinfunction "TX2P_3") (pintype "passive"))
    )
    (net (code "72") (name "/QSFP3_TX3_N") (class "Default")
      (node (ref "J6") (pin "34") (pinfunction "TX3N_34") (pintype "passive"))
    )
    (net (code "73") (name "/QSFP3_TX3_P") (class "Default")
      (node (ref "J6") (pin "33") (pinfunction "TX3P_33") (pintype "passive"))
    )
    (net (code "74") (name "/QSFP3_TX4_N") (class "Default")
      (node (ref "J6") (pin "5") (pinfunction "TX4N_5") (pintype "passive"))
    )
    (net (code "75") (name "/QSFP3_TX4_P") (class "Default")
      (node (ref "J6") (pin "6") (pinfunction "TX4P_6") (pintype "passive"))
    )
    (net (code "76") (name "/QSFP3_VCCI") (class "Default")
      (node (ref "C60") (pin "2") (pinfunction "2_2") (pintype "passive"))
      (node (ref "C61") (pin "2") (pinfunction "2_2") (pintype "passive"))
      (node (ref "FB13") (pin "2") (pintype "passive"))
      (node (ref "J6") (pin "30") (pinfunction "VCCI_30") (pintype "power_in"))
    )
    (net (code "77") (name "/QSFP3_VCCRX") (class "Default")
      (node (ref "C50") (pin "2") (pinfunction "2_2") (pintype "passive"))
      (node (ref "C51") (pin "2") (pinfunction "2_2") (pintype "passive"))
      (node (ref "FB9") (pin "2") (pintype "passive"))
      (node (ref "J6") (pin "10") (pinfunction "VCCRX_10") (pintype "power_in"))
    )
    (net (code "78") (name "/QSFP3_VCCTX") (class "Default")
      (node (ref "C56") (pin "2") (pinfunction "2_2") (pintype "passive"))
      (node (ref "C57") (pin "2") (pinfunction "2_2") (pintype "passive"))
      (node (ref "FB11") (pin "2") (pintype "passive"))
      (node (ref "J6") (pin "29") (pinfunction "VCCTX_29") (pintype "power_in"))
    )
    (net (code "79") (name "/QSFP4_INTL") (class "Default")
      (node (ref "J7") (pin "28") (pinfunction "INTL_28") (pintype "passive"))
      (node (ref "R64") (pin "1") (pintype "passive"))
    )
    (net (code "80") (name "/QSFP4_LPMODE") (class "Default")
      (node (ref "J7") (pin "31") (pinfunction "LPMODE_31") (pintype "passive"))
    )
    (net (code "81") (name "/QSFP4_MODPRSL") (class "Default")
      (node (ref "J7") (pin "27") (pinfunction "MODPRSL_27") (pintype "passive"))
      (node (ref "R63") (pin "1") (pintype "passive"))
    )
    (net (code "82") (name "/QSFP4_MODSELL") (class "Default")
      (node (ref "J7") (pin "8") (pinfunction "MODSELL_8") (pintype "passive"))
    )
    (net (code "83") (name "/QSFP4_RESETL") (class "Default")
      (node (ref "J7") (pin "9") (pinfunction "RESETL_9") (pintype "passive"))
      (node (ref "R62") (pin "1") (pintype "passive"))
    )
    (net (code "84") (name "/QSFP4_RX1_N") (class "Default")
      (node (ref "J7") (pin "18") (pinfunction "RX1N_18") (pintype "passive"))
    )
    (net (code "85") (name "/QSFP4_RX1_P") (class "Default")
      (node (ref "J7") (pin "17") (pinfunction "RX1P_17") (pintype "passive"))
    )
    (net (code "86") (name "/QSFP4_RX2_N") (class "Default")
      (node (ref "J7") (pin "21") (pinfunction "RX2N_21") (pintype "passive"))
    )
    (net (code "87") (name "/QSFP4_RX2_P") (class "Default")
      (node (ref "J7") (pin "22") (pinfunction "RX2P_22") (pintype "passive"))
    )
    (net (code "88") (name "/QSFP4_RX3_N") (class "Default")
      (node (ref "J7") (pin "15") (pinfunction "RX3N_15") (pintype "passive"))
    )
    (net (code "89") (name "/QSFP4_RX3_P") (class "Default")
      (node (ref "J7") (pin "14") (pinfunction "RX3P_14") (pintype "passive"))
    )
    (net (code "90") (name "/QSFP4_RX4_N") (class "Default")
      (node (ref "J7") (pin "24") (pinfunction "RX4N_24") (pintype "passive"))
    )
    (net (code "91") (name "/QSFP4_RX4_P") (class "Default")
      (node (ref "J7") (pin "25") (pinfunction "RX4P_25") (pintype "passive"))
    )
    (net (code "92") (name "/QSFP4_SCL") (class "Default")
      (node (ref "J7") (pin "11") (pinfunction "SCL_11") (pintype "input"))
    )
    (net (code "93") (name "/QSFP4_SDA") (class "Default")
      (node (ref "J7") (pin "12") (pinfunction "SDA_12") (pintype "bidirectional"))
    )
    (net (code "94") (name "/QSFP4_TX1_N") (class "Default")
      (node (ref "J7") (pin "37") (pinfunction "TX1N_37") (pintype "passive"))
    )
    (net (code "95") (name "/QSFP4_TX1_P") (class "Default")
      (node (ref "J7") (pin "36") (pinfunction "TX1P_36") (pintype "passive"))
    )
    (net (code "96") (name "/QSFP4_TX2_N") (class "Default")
      (node (ref "J7") (pin "2") (pinfunction "TX2N_2") (pintype "passive"))
    )
    (net (code "97") (name "/QSFP4_TX2_P") (class "Default")
      (node (ref "J7") (pin "3") (pinfunction "TX2P_3") (pintype "passive"))
    )
    (net (code "98") (name "/QSFP4_TX3_N") (class "Default")
      (node (ref "J7") (pin "34") (pinfunction "TX3N_34") (pintype "passive"))
    )
    (net (code "99") (name "/QSFP4_TX3_P") (class "Default")
      (node (ref "J7") (pin "33") (pinfunction "TX3P_33") (pintype "passive"))
    )
    (net (code "100") (name "/QSFP4_TX4_N") (class "Default")
      (node (ref "J7") (pin "5") (pinfunction "TX4N_5") (pintype "passive"))
    )
    (net (code "101") (name "/QSFP4_TX4_P") (class "Default")
      (node (ref "J7") (pin "6") (pinfunction "TX4P_6") (pintype "passive"))
    )
    (net (code "102") (name "/QSFP4_VCCI") (class "Default")
      (node (ref "C62") (pin "2") (pinfunction "2_2") (pintype "passive"))
      (node (ref "C63") (pin "2") (pinfunction "2_2") (pintype "passive"))
      (node (ref "FB14") (pin "2") (pintype "passive"))
      (node (ref "J7") (pin "30") (pinfunction "VCCI_30") (pintype "power_in"))
    )
    (net (code "103") (name "/QSFP4_VCCRX") (class "Default")
      (node (ref "C54") (pin "2") (pinfunction "2_2") (pintype "passive"))
      (node (ref "C55") (pin "2") (pinfunction "2_2") (pintype "passive"))
      (node (ref "FB10") (pin "2") (pintype "passive"))
      (node (ref "J7") (pin "10") (pinfunction "VCCRX_10") (pintype "power_in"))
    )
    (net (code "104") (name "/QSFP4_VCCTX") (class "Default")
      (node (ref "C58") (pin "2") (pinfunction "2_2") (pintype "passive"))
      (node (ref "C59") (pin "2") (pinfunction "2_2") (pintype "passive"))
      (node (ref "FB12") (pin "2") (pintype "passive"))
      (node (ref "J7") (pin "29") (pinfunction "VCCTX_29") (pintype "power_in"))
    )
    (net (code "105") (name "GND") (class "Default")
      (node (ref "C32") (pin "1") (pinfunction "1_1") (pintype "passive"))
      (node (ref "C33") (pin "1") (pinfunction "1_1") (pintype "passive"))
      (node (ref "C34") (pin "1") (pinfunction "1_1") (pintype "passive"))
      (node (ref "C35") (pin "1") (pinfunction "1_1") (pintype "passive"))
      (node (ref "C36") (pin "1") (pinfunction "1_1") (pintype "passive"))
      (node (ref "C37") (pin "1") (pinfunction "1_1") (pintype "passive"))
      (node (ref "C38") (pin "1") (pinfunction "1_1") (pintype "passive"))
      (node (ref "C39") (pin "1") (pinfunction "1_1") (pintype "passive"))
      (node (ref "C40") (pin "1") (pinfunction "1_1") (pintype "passive"))
      (node (ref "C41") (pin "1") (pinfunction "1_1") (pintype "passive"))
      (node (ref "C42") (pin "1") (pinfunction "1_1") (pintype "passive"))
      (node (ref "C43") (pin "1") (pinfunction "1_1") (pintype "passive"))
      (node (ref "C44") (pin "1") (pinfunction "1_1") (pintype "passive"))
      (node (ref "C45") (pin "1") (pinfunction "1_1") (pintype "passive"))
      (node (ref "C46") (pin "1") (pinfunction "1_1") (pintype "passive"))
      (node (ref "C47") (pin "1") (pinfunction "1_1") (pintype "passive"))
      (node (ref "C48") (pin "1") (pinfunction "1_1") (pintype "passive"))
      (node (ref "C49") (pin "1") (pinfunction "1_1") (pintype "passive"))
      (node (ref "C50") (pin "1") (pinfunction "1_1") (pintype "passive"))
      (node (ref "C51") (pin "1") (pinfunction "1_1") (pintype "passive"))
      (node (ref "C52") (pin "1") (pinfunction "1_1") (pintype "passive"))
      (node (ref "C53") (pin "1") (pinfunction "1_1") (pintype "passive"))
      (node (ref "C54") (pin "1") (pinfunction "1_1") (pintype "passive"))
      (node (ref "C55") (pin "1") (pinfunction "1_1") (pintype "passive"))
      (node (ref "C56") (pin "1") (pinfunction "1_1") (pintype "passive"))
      (node (ref "C57") (pin "1") (pinfunction "1_1") (pintype "passive"))
      (node (ref "C58") (pin "1") (pinfunction "1_1") (pintype "passive"))
      (node (ref "C59") (pin "1") (pinfunction "1_1") (pintype "passive"))
      (node (ref "C60") (pin "1") (pinfunction "1_1") (pintype "passive"))
      (node (ref "C61") (pin "1") (pinfunction "1_1") (pintype "passive"))
      (node (ref "C62") (pin "1") (pinfunction "1_1") (pintype "passive"))
      (node (ref "C63") (pin "1") (pinfunction "1_1") (pintype "passive"))
      (node (ref "J4") (pin "1") (pinfunction "GND1_1") (pintype "power_in"))
      (node (ref "J4") (pin "13") (pinfunction "GND4_13") (pintype "power_in"))
      (node (ref "J4") (pin "16") (pinfunction "GND5_16") (pintype "power_in"))
      (node (ref "J4") (pin "19") (pinfunction "GND6_19") (pintype "power_in"))
      (node (ref "J4") (pin "20") (pinfunction "GND7_20") (pintype "power_in"))
      (node (ref "J4") (pin "23") (pinfunction "GND8_23") (pintype "power_in"))
      (node (ref "J4") (pin "26") (pinfunction "GND9_26") (pintype "power_in"))
      (node (ref "J4") (pin "32") (pinfunction "GND10_32") (pintype "power_in"))
      (node (ref "J4") (pin "35") (pinfunction "GND11_35") (pintype "power_in"))
      (node (ref "J4") (pin "38") (pinfunction "GND12_38") (pintype "power_in"))
      (node (ref "J4") (pin "4") (pinfunction "GND2_4") (pintype "power_in"))
      (node (ref "J4") (pin "7") (pinfunction "GND3_7") (pintype "power_in"))
      (node (ref "J5") (pin "1") (pinfunction "GND1_1") (pintype "power_in"))
      (node (ref "J5") (pin "13") (pinfunction "GND4_13") (pintype "power_in"))
      (node (ref "J5") (pin "16") (pinfunction "GND5_16") (pintype "power_in"))
      (node (ref "J5") (pin "19") (pinfunction "GND6_19") (pintype "power_in"))
      (node (ref "J5") (pin "20") (pinfunction "GND7_20") (pintype "power_in"))
      (node (ref "J5") (pin "23") (pinfunction "GND8_23") (pintype "power_in"))
      (node (ref "J5") (pin "26") (pinfunction "GND9_26") (pintype "power_in"))
      (node (ref "J5") (pin "32") (pinfunction "GND10_32") (pintype "power_in"))
      (node (ref "J5") (pin "35") (pinfunction "GND11_35") (pintype "power_in"))
      (node (ref "J5") (pin "38") (pinfunction "GND12_38") (pintype "power_in"))
      (node (ref "J5") (pin "4") (pinfunction "GND2_4") (pintype "power_in"))
      (node (ref "J5") (pin "7") (pinfunction "GND3_7") (pintype "power_in"))
      (node (ref "J6") (pin "1") (pinfunction "GND1_1") (pintype "power_in"))
      (node (ref "J6") (pin "13") (pinfunction "GND4_13") (pintype "power_in"))
      (node (ref "J6") (pin "16") (pinfunction "GND5_16") (pintype "power_in"))
      (node (ref "J6") (pin "19") (pinfunction "GND6_19") (pintype "power_in"))
      (node (ref "J6") (pin "20") (pinfunction "GND7_20") (pintype "power_in"))
      (node (ref "J6") (pin "23") (pinfunction "GND8_23") (pintype "power_in"))
      (node (ref "J6") (pin "26") (pinfunction "GND9_26") (pintype "power_in"))
      (node (ref "J6") (pin "32") (pinfunction "GND10_32") (pintype "power_in"))
      (node (ref "J6") (pin "35") (pinfunction "GND11_35") (pintype "power_in"))
      (node (ref "J6") (pin "38") (pinfunction "GND12_38") (pintype "power_in"))
      (node (ref "J6") (pin "4") (pinfunction "GND2_4") (pintype "power_in"))
      (node (ref "J6") (pin "7") (pinfunction "GND3_7") (pintype "power_in"))
      (node (ref "J7") (pin "1") (pinfunction "GND1_1") (pintype "power_in"))
      (node (ref "J7") (pin "13") (pinfunction "GND4_13") (pintype "power_in"))
      (node (ref "J7") (pin "16") (pinfunction "GND5_16") (pintype "power_in"))
      (node (ref "J7") (pin "19") (pinfunction "GND6_19") (pintype "power_in"))
      (node (ref "J7") (pin "20") (pinfunction "GND7_20") (pintype "power_in"))
      (node (ref "J7") (pin "23") (pinfunction "GND8_23") (pintype "power_in"))
      (node (ref "J7") (pin "26") (pinfunction "GND9_26") (pintype "power_in"))
      (node (ref "J7") (pin "32") (pinfunction "GND10_32") (pintype "power_in"))
      (node (ref "J7") (pin "35") (pinfunction "GND11_35") (pintype "power_in"))
      (node (ref "J7") (pin "38") (pinfunction "GND12_38") (pintype "power_in"))
      (node (ref "J7") (pin "4") (pinfunction "GND2_4") (pintype "power_in"))
      (node (ref "J7") (pin "7") (pinfunction "GND3_7") (pintype "power_in"))
    )
    (net (code "106") (name "UTIL_3V3") (class "Default")
      (node (ref "C34") (pin "2") (pinfunction "2_2") (pintype "passive"))
      (node (ref "C35") (pin "2") (pinfunction "2_2") (pintype "passive"))
      (node (ref "C36") (pin "2") (pinfunction "2_2") (pintype "passive"))
      (node (ref "C37") (pin "2") (pinfunction "2_2") (pintype "passive"))
      (node (ref "C48") (pin "2") (pinfunction "2_2") (pintype "passive"))
      (node (ref "C49") (pin "2") (pinfunction "2_2") (pintype "passive"))
      (node (ref "C52") (pin "2") (pinfunction "2_2") (pintype "passive"))
      (node (ref "C53") (pin "2") (pinfunction "2_2") (pintype "passive"))
      (node (ref "FB10") (pin "1") (pintype "passive"))
      (node (ref "FB11") (pin "1") (pintype "passive"))
      (node (ref "FB12") (pin "1") (pintype "passive"))
      (node (ref "FB13") (pin "1") (pintype "passive"))
      (node (ref "FB14") (pin "1") (pintype "passive"))
      (node (ref "FB3") (pin "1") (pintype "passive"))
      (node (ref "FB4") (pin "1") (pintype "passive"))
      (node (ref "FB5") (pin "1") (pintype "passive"))
      (node (ref "FB6") (pin "1") (pintype "passive"))
      (node (ref "FB7") (pin "1") (pintype "passive"))
      (node (ref "FB8") (pin "1") (pintype "passive"))
      (node (ref "FB9") (pin "1") (pintype "passive"))
      (node (ref "R53") (pin "2") (pintype "passive"))
      (node (ref "R54") (pin "2") (pintype "passive"))
      (node (ref "R55") (pin "2") (pintype "passive"))
      (node (ref "R56") (pin "2") (pintype "passive"))
      (node (ref "R57") (pin "2") (pintype "passive"))
      (node (ref "R58") (pin "2") (pintype "passive"))
      (node (ref "R59") (pin "2") (pintype "passive"))
      (node (ref "R60") (pin "2") (pintype "passive"))
      (node (ref "R61") (pin "2") (pintype "passive"))
      (node (ref "R62") (pin "2") (pintype "passive"))
      (node (ref "R63") (pin "2") (pintype "passive"))
      (node (ref "R64") (pin "2") (pintype "passive"))
    )
  )
)
